# Real_Time_Clock.net
KiCad netlist of a schematic drawn in Altium Designer
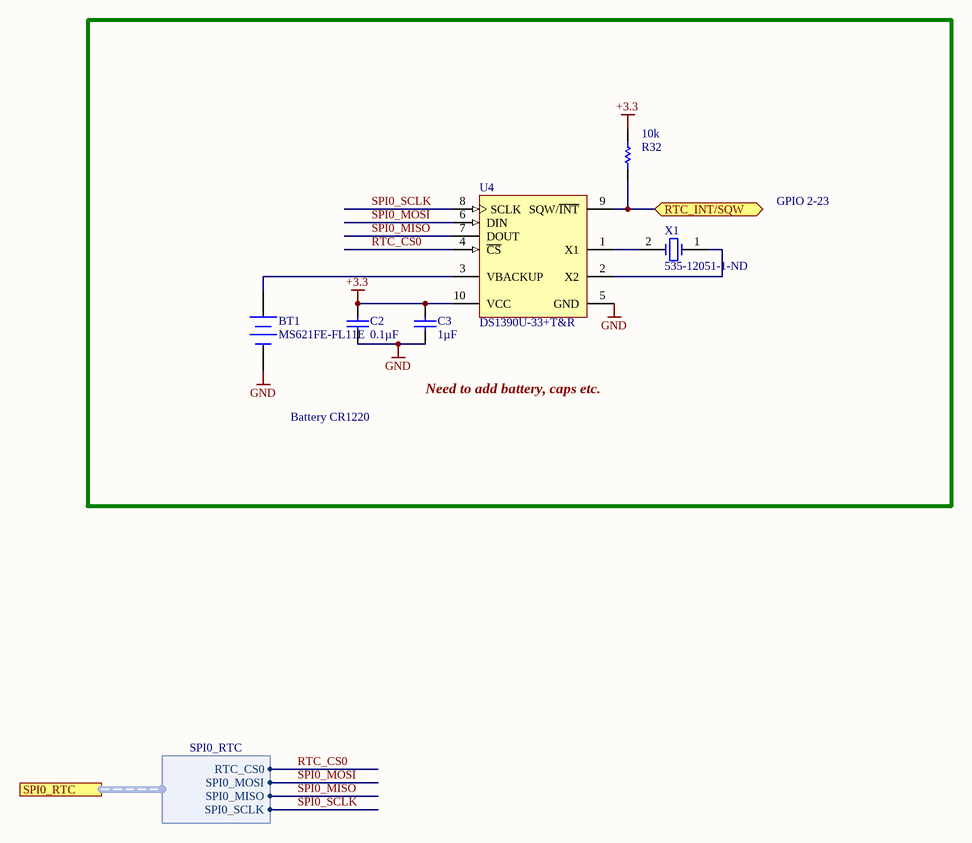
[diagram p0: Real Time Clock.SchDoc]

(export (version "E")
  (design (tool "Eeschema 10.0.6"))
  (components
    (comp (ref "BT1")
      (value "MS621FE-FL11E")
      (footprint "SEIK-MS621FE-FL11E-2_V")
      (description "MS Lihium Rechargeable Battery, 3 V, -20 to 60 degC, Tray")
      (fields (field (name "MANUFACTURER") "SeikoInstruments"))
      (libsource (lib "Altium Content Vault") (part "CMP-2000-05342-1"))
    )
    (comp (ref "C2")
      (value "CAP 100nF 25V 0805(2012)")
      (footprint "CAPC0805(2012)100_N")
      (description "CAP 100nF 25V -20% to +80% 0805 (2012 Metric) Thickness 1mm SMD")
      (fields
        (field (name "MANUFACTURER") "Murata Electronics North America")
        (field (name "MANUFACTURER PART NUMBER") "GRM21BR71E104KA01L")
        (field (name "CAPACITANCE") "0.1µF")
      )
      (libsource (lib "Altium Content Vault") (part "CMP-1036-04416-1"))
    )
    (comp (ref "C3")
      (value "CAP 1uF 25V 0805(2012)")
      (footprint "CAPC0805(2012)100_M")
      (description "CAP 1uF 25V ±10% 0805 (2012 Metric) Thickness 1mm SMD")
      (fields
        (field (name "MANUFACTURER") "Murata Electronics North America")
        (field (name "MANUFACTURER PART NUMBER") "GRM21BR71E105KA99L")
        (field (name "CAPACITANCE") "1µF")
      )
      (libsource (lib "Altium Content Vault") (part "CMP-1036-04754-1"))
    )
    (comp (ref "R32")
      (value "RES SMD TBD OHM 1% 1/8W 0805")
      (footprint "RESC0805(2012)_N")
      (fields (field (name "RESISTANCE (OHMS)") "10k"))
      (libsource (lib "Altium Content Vault") (part "CMP-1013-00393-1"))
    )
    (comp (ref "U4")
      (value "DS1390U-33+T&R")
      (footprint "U10+2_L")
      (description "SPI Real-Time Clock with Trickle Charger, 3.3V, 10-Pin uSOP, -40 to 85 degC, Pb-Free, Reel")
      (libsource (lib "Altium Content Vault") (part "CMP-0254-00498-1"))
    )
    (comp (ref "X1")
      (value "AB26TRQ-32.768KHZ-T")
      (footprint "AB26TRQ-32.768KHZ-T")
      (fields (field (name "SUPPLIER PART NUMBER 1") "535-12051-1-ND"))
      (libsource (lib "ZLS_Schematic_lib") (part "AB26TRQ-32.768KHZ-T"))
    )
  )
  (nets
    (net (code "2") (name "+3.3") (class "Default")
      (node (ref "C2") (pin "2") (pinfunction "2_2") (pintype "passive"))
      (node (ref "C3") (pin "2") (pinfunction "2_2") (pintype "passive"))
      (node (ref "R32") (pin "1") (pinfunction "1_1") (pintype "passive"))
      (node (ref "U4") (pin "10") (pinfunction "VCC_10") (pintype "power_in"))
    )
    (net (code "3") (name "/RTC_CS0") (class "Default")
      (node (ref "U4") (pin "4") (pinfunction "~{CS}_4") (pintype "input"))
    )
    (net (code "4") (name "/RTC_INT{slash}SQW") (class "Default")
      (node (ref "R32") (pin "2") (pinfunction "2_2") (pintype "passive"))
      (node (ref "U4") (pin "9") (pinfunction "SQW/~{INT}_9") (pintype "open_collector"))
    )
    (net (code "5") (name "/SPI0_MISO") (class "Default")
      (node (ref "U4") (pin "7") (pinfunction "DOUT_7") (pintype "tri_state"))
    )
    (net (code "6") (name "/SPI0_MOSI") (class "Default")
      (node (ref "U4") (pin "6") (pinfunction "DIN_6") (pintype "input"))
    )
    (net (code "7") (name "/SPI0_SCLK") (class "Default")
      (node (ref "U4") (pin "8") (pinfunction "SCLK_8") (pintype "input"))
    )
    (net (code "9") (name "GND") (class "Default")
      (node (ref "BT1") (pin "2") (pinfunction "-_2") (pintype "passive"))
      (node (ref "C2") (pin "1") (pinfunction "1_1") (pintype "passive"))
      (node (ref "C3") (pin "1") (pinfunction "1_1") (pintype "passive"))
      (node (ref "U4") (pin "5") (pinfunction "GND_5") (pintype "power_in"))
    )
    (net (code "10") (name "Net-(BT1-+)") (class "Default")
      (node (ref "BT1") (pin "1") (pinfunction "+_1") (pintype "passive"))
      (node (ref "U4") (pin "3") (pinfunction "VBACKUP_3") (pintype "power_in"))
    )
    (net (code "11") (name "Net-(U4-X1)") (class "Default")
      (node (ref "U4") (pin "1") (pinfunction "X1_1") (pintype "passive"))
      (node (ref "X1") (pin "2") (pinfunction "2_2") (pintype "passive"))
    )
    (net (code "12") (name "Net-(U4-X2)") (class "Default")
      (node (ref "U4") (pin "2") (pinfunction "X2_2") (pintype "passive"))
      (node (ref "X1") (pin "1") (pinfunction "1_1") (pintype "passive"))
    )
  )
)
